# OpenBook_Reader.net
KiCad netlist of a schematic drawn in EAGLE
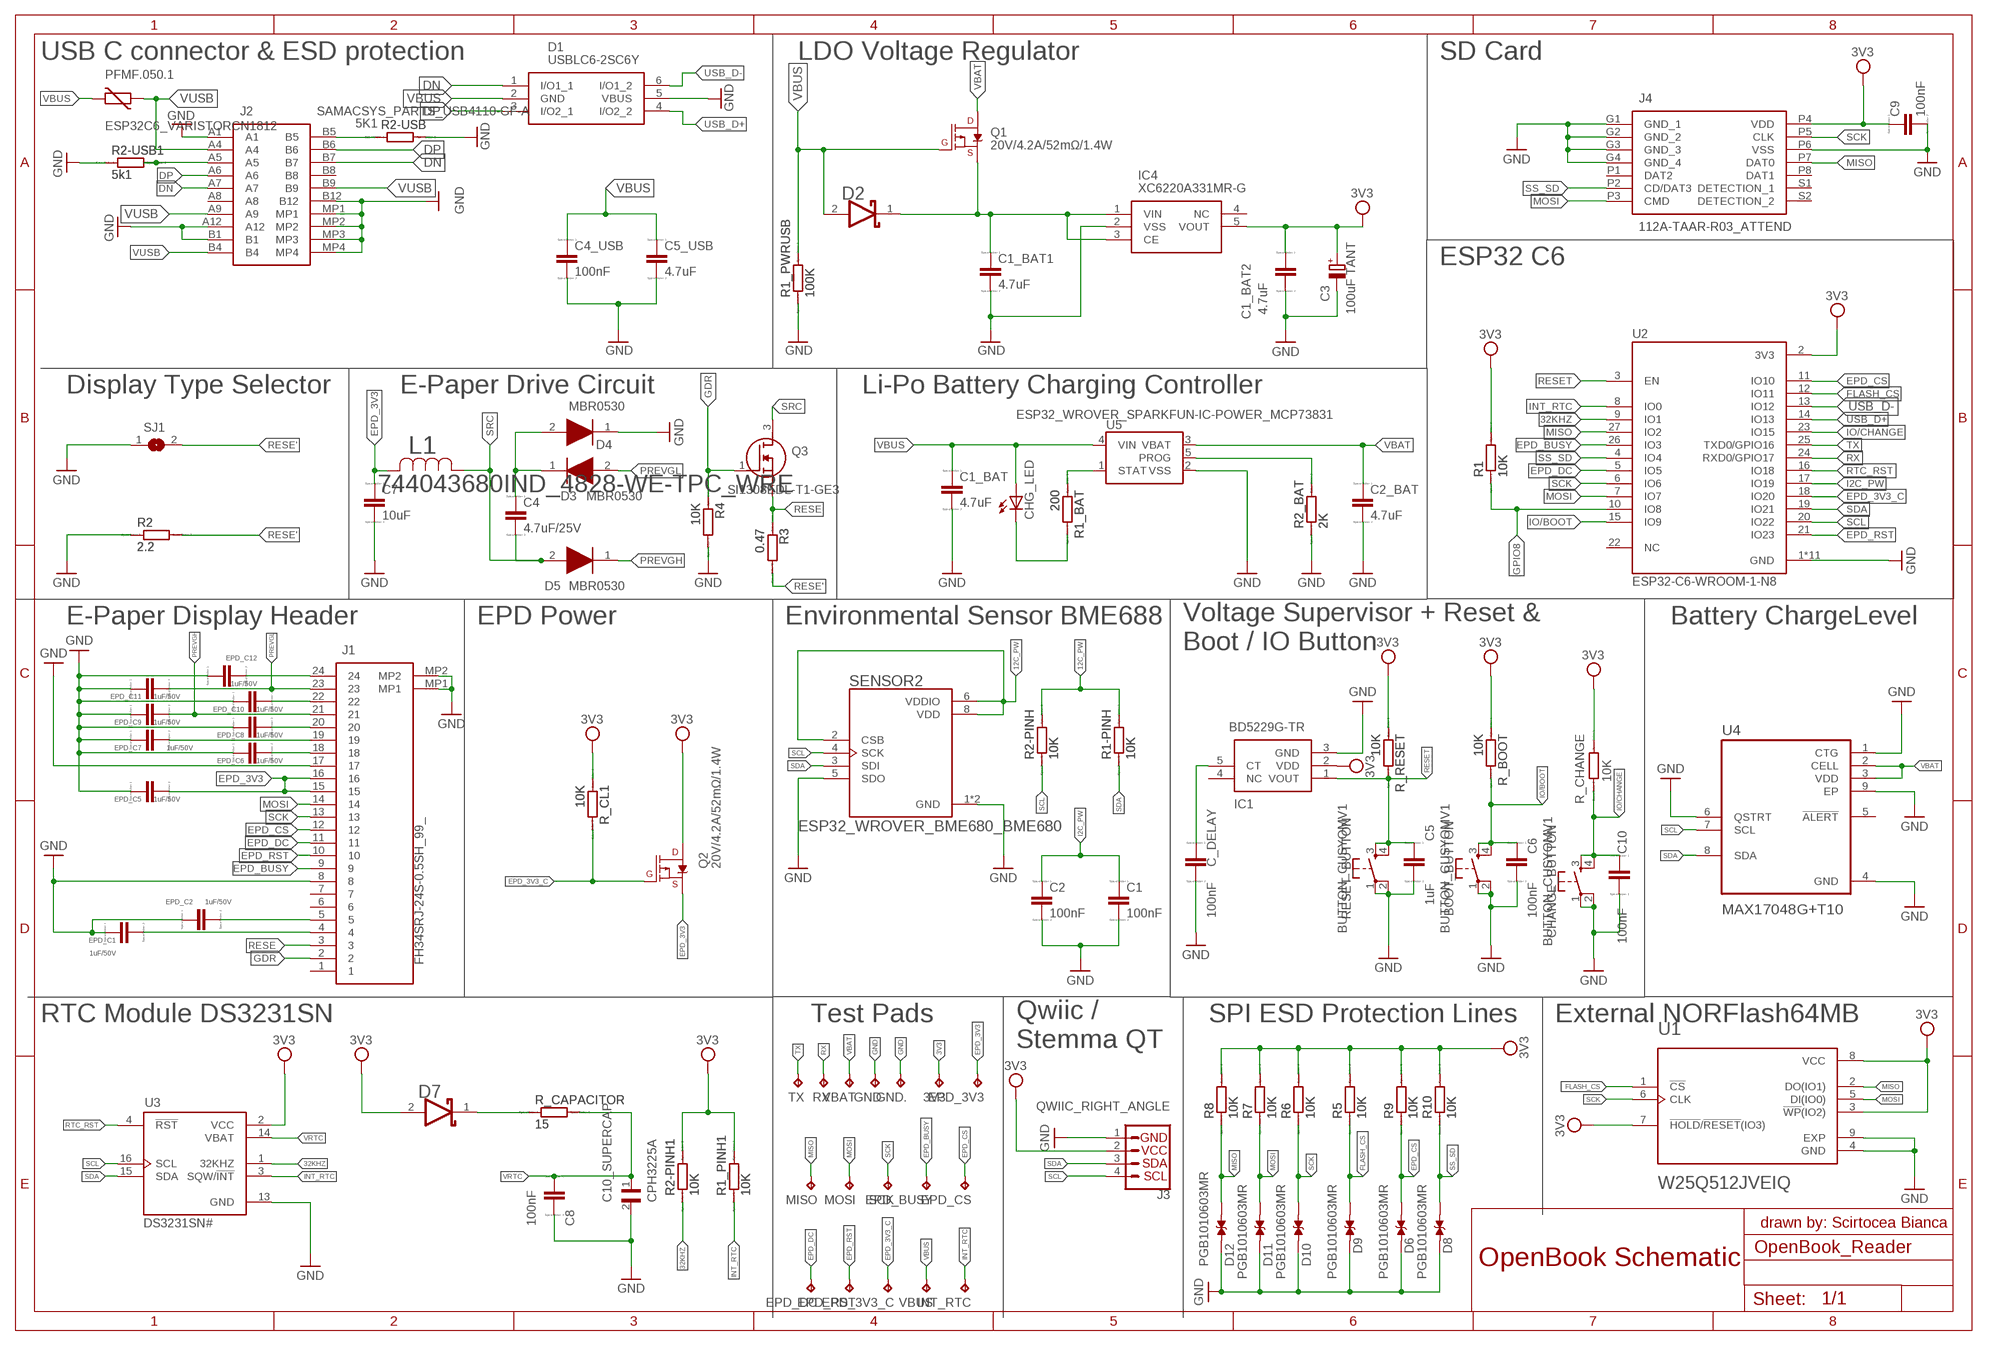
[diagram p0: schematic, sheet 1]

(export (version "E")
  (design (tool "Eeschema 10.0.6"))
  (components
    (comp (ref "3V3")
      (value "TPTP20R")
      (footprint "eagle-import:TP20R")
      (libsource (lib "eagle-import") (part "TPTP20R"))
    )
    (comp (ref "BOOT_BUTTON")
      (value "BUTTON_CUSYOMV1")
      (footprint "eagle-import:MYBUTTON")
      (libsource (lib "eagle-import") (part "BUTTON_CUSYOMV1"))
    )
    (comp (ref "C1")
      (value "100nF")
      (footprint "eagle-import:EAGLE-LTSPICE_C0402")
      (libsource (lib "eagle-import") (part "EAGLE-LTSPICE_CC0402"))
    )
    (comp (ref "C1_BAT")
      (value "4.7uF")
      (footprint "eagle-import:EAGLE-LTSPICE_C0402")
      (libsource (lib "eagle-import") (part "EAGLE-LTSPICE_CC0402"))
    )
    (comp (ref "C1_BAT1")
      (value "4.7uF")
      (footprint "eagle-import:EAGLE-LTSPICE_C0402")
      (libsource (lib "eagle-import") (part "EAGLE-LTSPICE_CC0402"))
    )
    (comp (ref "C1_BAT2")
      (value "4.7uF")
      (footprint "eagle-import:EAGLE-LTSPICE_C0402")
      (libsource (lib "eagle-import") (part "EAGLE-LTSPICE_CC0402"))
    )
    (comp (ref "C2")
      (value "100nF")
      (footprint "eagle-import:EAGLE-LTSPICE_C0402")
      (libsource (lib "eagle-import") (part "EAGLE-LTSPICE_CC0402"))
    )
    (comp (ref "C2_BAT")
      (value "4.7uF")
      (footprint "eagle-import:EAGLE-LTSPICE_C0402")
      (libsource (lib "eagle-import") (part "EAGLE-LTSPICE_CC0402"))
    )
    (comp (ref "C3")
      (value "100uF TANT")
      (footprint "eagle-import:RCL_CT3528")
      (libsource (lib "eagle-import") (part "RCL_CPOL-EUCT3528"))
    )
    (comp (ref "C4")
      (value "4.7uF/25V")
      (footprint "eagle-import:EAGLE-LTSPICE_C0402")
      (libsource (lib "eagle-import") (part "EAGLE-LTSPICE_CC0402"))
    )
    (comp (ref "C4_USB")
      (value "100nF")
      (footprint "eagle-import:EAGLE-LTSPICE_C0402")
      (libsource (lib "eagle-import") (part "EAGLE-LTSPICE_CC0402"))
    )
    (comp (ref "C5")
      (value "1uF")
      (footprint "eagle-import:EAGLE-LTSPICE_C0402")
      (libsource (lib "eagle-import") (part "EAGLE-LTSPICE_CC0402"))
    )
    (comp (ref "C5_USB")
      (value "4.7uF")
      (footprint "eagle-import:EAGLE-LTSPICE_C0402")
      (libsource (lib "eagle-import") (part "EAGLE-LTSPICE_CC0402"))
    )
    (comp (ref "C6")
      (value "100nF")
      (footprint "eagle-import:EAGLE-LTSPICE_C0402")
      (libsource (lib "eagle-import") (part "EAGLE-LTSPICE_CC0402"))
    )
    (comp (ref "C7")
      (value "10uF")
      (footprint "eagle-import:EAGLE-LTSPICE_C0402")
      (libsource (lib "eagle-import") (part "EAGLE-LTSPICE_CC0402"))
    )
    (comp (ref "C8")
      (value "100nF")
      (footprint "eagle-import:EAGLE-LTSPICE_C0402")
      (libsource (lib "eagle-import") (part "EAGLE-LTSPICE_CC0402"))
    )
    (comp (ref "C9")
      (value "100nF")
      (footprint "eagle-import:EAGLE-LTSPICE_C0402")
      (libsource (lib "eagle-import") (part "EAGLE-LTSPICE_CC0402"))
    )
    (comp (ref "C10")
      (value "100nF")
      (footprint "eagle-import:EAGLE-LTSPICE_C0402")
      (libsource (lib "eagle-import") (part "EAGLE-LTSPICE_CC0402"))
    )
    (comp (ref "C10_SUPERCAP")
      (value "CPH3225A")
      (footprint "eagle-import:CAPCP3225X100N")
      (fields (field (name "MF") "Seiko Instruments"))
      (libsource (lib "eagle-import") (part "CPH3225A"))
    )
    (comp (ref "CHANGE_BUTTON")
      (value "BUTTON_CUSYOMV1")
      (footprint "eagle-import:MYBUTTON")
      (libsource (lib "eagle-import") (part "BUTTON_CUSYOMV1"))
    )
    (comp (ref "CHG_LED")
      (value "ADAFRUIT_LEDCHIP-LED0603")
      (footprint "eagle-import:ADAFRUIT_CHIP-LED0603")
      (libsource (lib "eagle-import") (part "ADAFRUIT_LEDCHIP-LED0603"))
    )
    (comp (ref "C_DELAY")
      (value "100nF")
      (footprint "eagle-import:EAGLE-LTSPICE_C0402")
      (libsource (lib "eagle-import") (part "EAGLE-LTSPICE_CC0402"))
    )
    (comp (ref "D1")
      (value "USBLC6-2SC6Y")
      (footprint "eagle-import:SOT95P280X145-6N")
      (fields (field (name "MF") "STMicroelectronics"))
      (libsource (lib "eagle-import") (part "USBLC6-2SC6Y"))
    )
    (comp (ref "D2")
      (value "ESP32_WROVER_AVX---SD0805S020S1R0_AVX_SD0805S020S1R0_0_0AVX_SD0805S020S1R0_0_0")
      (footprint "eagle-import:ESP32_WROVER_AVX---SD0805S020S1R0_AVX_SD0805S020S1R0_0")
      (fields
        (field (name "DIGIKEY_PART_NUMBER") "478-7800-1-ND")
        (field (name "MF") "AVX")
        (field (name "MOUSER_PART_NUMBER") "581-SD0805S020S1R0")
      )
      (libsource (lib "eagle-import") (part "ESP32_WROVER_AVX---SD0805S020S1R0_AVX_SD0805S020S1R0_0_0AVX_SD0805S020S1R0_0_0"))
    )
    (comp (ref "D3")
      (value "MBR0530")
      (footprint "eagle-import:SOD3716X135N")
      (fields (field (name "MF") "ON Semiconductor"))
      (libsource (lib "eagle-import") (part "MBR0530"))
    )
    (comp (ref "D4")
      (value "MBR0530")
      (footprint "eagle-import:SOD3716X135N")
      (fields (field (name "MF") "ON Semiconductor"))
      (libsource (lib "eagle-import") (part "MBR0530"))
    )
    (comp (ref "D5")
      (value "MBR0530")
      (footprint "eagle-import:SOD3716X135N")
      (fields (field (name "MF") "ON Semiconductor"))
      (libsource (lib "eagle-import") (part "MBR0530"))
    )
    (comp (ref "D6")
      (value "PGB1010603MR")
      (footprint "eagle-import:DIOC1608X36N")
      (fields (field (name "MF") "Littelfuse Inc."))
      (libsource (lib "eagle-import") (part "PGB1010603MR"))
    )
    (comp (ref "D7")
      (value "ESP32_WROVER_AVX---SD0805S020S1R0_AVX_SD0805S020S1R0_0_0AVX_SD0805S020S1R0_0_0")
      (footprint "eagle-import:ESP32_WROVER_AVX---SD0805S020S1R0_AVX_SD0805S020S1R0_0")
      (fields
        (field (name "DIGIKEY_PART_NUMBER") "478-7800-1-ND")
        (field (name "MF") "AVX")
        (field (name "MOUSER_PART_NUMBER") "581-SD0805S020S1R0")
      )
      (libsource (lib "eagle-import") (part "ESP32_WROVER_AVX---SD0805S020S1R0_AVX_SD0805S020S1R0_0_0AVX_SD0805S020S1R0_0_0"))
    )
    (comp (ref "D8")
      (value "PGB1010603MR")
      (footprint "eagle-import:DIOC1608X36N")
      (fields (field (name "MF") "Littelfuse Inc."))
      (libsource (lib "eagle-import") (part "PGB1010603MR"))
    )
    (comp (ref "D9")
      (value "PGB1010603MR")
      (footprint "eagle-import:DIOC1608X36N")
      (fields (field (name "MF") "Littelfuse Inc."))
      (libsource (lib "eagle-import") (part "PGB1010603MR"))
    )
    (comp (ref "D10")
      (value "PGB1010603MR")
      (footprint "eagle-import:DIOC1608X36N")
      (fields (field (name "MF") "Littelfuse Inc."))
      (libsource (lib "eagle-import") (part "PGB1010603MR"))
    )
    (comp (ref "D11")
      (value "PGB1010603MR")
      (footprint "eagle-import:DIOC1608X36N")
      (fields (field (name "MF") "Littelfuse Inc."))
      (libsource (lib "eagle-import") (part "PGB1010603MR"))
    )
    (comp (ref "D12")
      (value "PGB1010603MR")
      (footprint "eagle-import:DIOC1608X36N")
      (fields (field (name "MF") "Littelfuse Inc."))
      (libsource (lib "eagle-import") (part "PGB1010603MR"))
    )
    (comp (ref "EPD_3V3")
      (value "TPTP20R")
      (footprint "eagle-import:TP20R")
      (libsource (lib "eagle-import") (part "TPTP20R"))
    )
    (comp (ref "EPD_3V3_C")
      (value "TPTP20R")
      (footprint "eagle-import:TP20R")
      (libsource (lib "eagle-import") (part "TPTP20R"))
    )
    (comp (ref "EPD_BUSY")
      (value "TPTP20R")
      (footprint "eagle-import:TP20R")
      (libsource (lib "eagle-import") (part "TPTP20R"))
    )
    (comp (ref "EPD_C1")
      (value "1uF/50V")
      (footprint "eagle-import:EAGLE-LTSPICE_C0402")
      (libsource (lib "eagle-import") (part "EAGLE-LTSPICE_CC0402"))
    )
    (comp (ref "EPD_C2")
      (value "1uF/50V")
      (footprint "eagle-import:EAGLE-LTSPICE_C0402")
      (libsource (lib "eagle-import") (part "EAGLE-LTSPICE_CC0402"))
    )
    (comp (ref "EPD_C5")
      (value "1uF/50V")
      (footprint "eagle-import:EAGLE-LTSPICE_C0402")
      (libsource (lib "eagle-import") (part "EAGLE-LTSPICE_CC0402"))
    )
    (comp (ref "EPD_C6")
      (value "1uF/50V")
      (footprint "eagle-import:EAGLE-LTSPICE_C0402")
      (libsource (lib "eagle-import") (part "EAGLE-LTSPICE_CC0402"))
    )
    (comp (ref "EPD_C7")
      (value "1uF/50V")
      (footprint "eagle-import:EAGLE-LTSPICE_C0402")
      (libsource (lib "eagle-import") (part "EAGLE-LTSPICE_CC0402"))
    )
    (comp (ref "EPD_C8")
      (value "1uF/50V")
      (footprint "eagle-import:EAGLE-LTSPICE_C0402")
      (libsource (lib "eagle-import") (part "EAGLE-LTSPICE_CC0402"))
    )
    (comp (ref "EPD_C9")
      (value "1uF/50V")
      (footprint "eagle-import:EAGLE-LTSPICE_C0402")
      (libsource (lib "eagle-import") (part "EAGLE-LTSPICE_CC0402"))
    )
    (comp (ref "EPD_C10")
      (value "1uF/50V")
      (footprint "eagle-import:EAGLE-LTSPICE_C0402")
      (libsource (lib "eagle-import") (part "EAGLE-LTSPICE_CC0402"))
    )
    (comp (ref "EPD_C11")
      (value "1uF/50V")
      (footprint "eagle-import:EAGLE-LTSPICE_C0402")
      (libsource (lib "eagle-import") (part "EAGLE-LTSPICE_CC0402"))
    )
    (comp (ref "EPD_C12")
      (value "1uF/50V")
      (footprint "eagle-import:EAGLE-LTSPICE_C0402")
      (libsource (lib "eagle-import") (part "EAGLE-LTSPICE_CC0402"))
    )
    (comp (ref "EPD_CS")
      (value "TPTP20R")
      (footprint "eagle-import:TP20R")
      (libsource (lib "eagle-import") (part "TPTP20R"))
    )
    (comp (ref "EPD_DC")
      (value "TPTP20R")
      (footprint "eagle-import:TP20R")
      (libsource (lib "eagle-import") (part "TPTP20R"))
    )
    (comp (ref "EPD_RST")
      (value "TPTP20R")
      (footprint "eagle-import:TP20R")
      (libsource (lib "eagle-import") (part "TPTP20R"))
    )
    (comp (ref "GND")
      (value "TPTP20R")
      (footprint "eagle-import:TP20R")
      (libsource (lib "eagle-import") (part "TPTP20R"))
    )
    (comp (ref "GND.")
      (value "TPTP20R")
      (footprint "eagle-import:TP20R")
      (libsource (lib "eagle-import") (part "TPTP20R"))
    )
    (comp (ref "IC1")
      (value "BD5229G-TR")
      (footprint "eagle-import:SOT95P280X125-5N")
      (fields (field (name "MOUSER_PART_NUMBER") "755-BD5229G-TR"))
      (libsource (lib "eagle-import") (part "BD5229G-TR"))
    )
    (comp (ref "IC4")
      (value "XC6220A331MR-G")
      (footprint "eagle-import:SOT95P280X120-5N")
      (fields (field (name "MOUSER_PART_NUMBER") "865-XC6220A331MR-G"))
      (libsource (lib "eagle-import") (part "XC6220A331MR-G"))
    )
    (comp (ref "INT_RTC")
      (value "TPTP20R")
      (footprint "eagle-import:TP20R")
      (libsource (lib "eagle-import") (part "TPTP20R"))
    )
    (comp (ref "J1")
      (value "FH34SRJ-24S-0.5SH_99_")
      (footprint "eagle-import:FH34SRJ24S05SH99")
      (fields
        (field (name "MANUFACTURER_PART_NUMBER") "FH34SRJ-24S-0.5SH(99)")
        (field (name "MOUSER_PART_NUMBER") "798-FH34SRJ24S05SH99")
      )
      (libsource (lib "eagle-import") (part "FH34SRJ-24S-0.5SH_99_"))
    )
    (comp (ref "J2")
      (value "SAMACSYS_PARTS_USB4110-GF-A")
      (footprint "eagle-import:SAMACSYS_PARTS_USB4110GFA")
      (fields
        (field (name "MANUFACTURER_PART_NUMBER") "USB4110-GF-A")
        (field (name "MOUSER_PART_NUMBER") "640-USB4110-GF-A")
      )
      (libsource (lib "eagle-import") (part "SAMACSYS_PARTS_USB4110-GF-A"))
    )
    (comp (ref "J3")
      (value "QWIIC_RIGHT_ANGLE")
      (footprint "eagle-import:JST04_1MM_RA")
      (libsource (lib "eagle-import") (part "QWIIC_CONNECTORJS-1MM"))
    )
    (comp (ref "J4")
      (value "112A-TAAR-R03_ATTEND")
      (footprint "eagle-import:112ATAARR03ATTEND")
      (fields (field (name "MANUFACTURER_PART_NUMBER") "112A-TAAR-R03 ATTEND"))
      (libsource (lib "eagle-import") (part "112A-TAAR-R03_ATTEND"))
    )
    (comp (ref "L1")
      (value "744043680IND_4828-WE-TPC_WRE")
      (footprint "eagle-import:IND_4828-WE-TPC_WRE")
      (fields
        (field (name "MANUFACTURER_PART_NUMBER") "744043680")
        (field (name "COPYRIGHT") "Copyright (C) 2024 Ultra Librarian. All rights reserved.")
      )
      (libsource (lib "eagle-import") (part "744043680IND_4828-WE-TPC_WRE"))
    )
    (comp (ref "MISO")
      (value "TPTP20R")
      (footprint "eagle-import:TP20R")
      (libsource (lib "eagle-import") (part "TPTP20R"))
    )
    (comp (ref "MOSI")
      (value "TPTP20R")
      (footprint "eagle-import:TP20R")
      (libsource (lib "eagle-import") (part "TPTP20R"))
    )
    (comp (ref "PFMF.050.1")
      (value "ESP32C6_VARISTORCN1812")
      (footprint "eagle-import:ESP32C6_VARISTOR_CT_CN1812")
      (libsource (lib "eagle-import") (part "ESP32C6_VARISTORCN1812"))
    )
    (comp (ref "Q1")
      (value "20V/4.2A/52mΩ/1.4W")
      (footprint "eagle-import:ESP32_WROVER_SPARKFUN-DISCRETESEMI_SOT23-3")
      (libsource (lib "eagle-import") (part "ESP32_WROVER_SPARKFUN-DISCRETESEMI_MOSFET_PCH-DMG2305UX-7"))
    )
    (comp (ref "Q2")
      (value "20V/4.2A/52mΩ/1.4W")
      (footprint "eagle-import:ESP32_WROVER_SPARKFUN-DISCRETESEMI_SOT23-3")
      (libsource (lib "eagle-import") (part "ESP32_WROVER_SPARKFUN-DISCRETESEMI_MOSFET_PCH-DMG2305UX-7"))
    )
    (comp (ref "Q3")
      (value "SI1308EDL-T1-GE3")
      (footprint "eagle-import:SOT65P210X110-3N")
      (fields (field (name "MF") "Vishay Siliconix"))
      (libsource (lib "eagle-import") (part "SI1308EDL-T1-GE3"))
    )
    (comp (ref "R1")
      (value "10K")
      (footprint "eagle-import:ESP32_WROVER_EAGLE-LTSPICE_R0402")
      (libsource (lib "eagle-import") (part "ESP32_WROVER_EAGLE-LTSPICE_RR0402"))
    )
    (comp (ref "R1-PINH")
      (value "10K")
      (footprint "eagle-import:ESP32_WROVER_EAGLE-LTSPICE_R0402")
      (libsource (lib "eagle-import") (part "ESP32_WROVER_EAGLE-LTSPICE_RR0402"))
    )
    (comp (ref "R1_BAT")
      (value "200")
      (footprint "eagle-import:ESP32_WROVER_EAGLE-LTSPICE_R0402")
      (libsource (lib "eagle-import") (part "ESP32_WROVER_EAGLE-LTSPICE_RR0402"))
    )
    (comp (ref "R1_PINH1")
      (value "10K")
      (footprint "eagle-import:ESP32_WROVER_EAGLE-LTSPICE_R0402")
      (libsource (lib "eagle-import") (part "ESP32_WROVER_EAGLE-LTSPICE_RR0402"))
    )
    (comp (ref "R1_PWRUSB")
      (value "100K")
      (footprint "eagle-import:ESP32_WROVER_EAGLE-LTSPICE_R0402")
      (libsource (lib "eagle-import") (part "ESP32_WROVER_EAGLE-LTSPICE_RR0402"))
    )
    (comp (ref "R2")
      (value "2.2")
      (footprint "eagle-import:ESP32_WROVER_EAGLE-LTSPICE_R0402")
      (libsource (lib "eagle-import") (part "ESP32_WROVER_EAGLE-LTSPICE_RR0402"))
    )
    (comp (ref "R2-PINH")
      (value "10K")
      (footprint "eagle-import:ESP32_WROVER_EAGLE-LTSPICE_R0402")
      (libsource (lib "eagle-import") (part "ESP32_WROVER_EAGLE-LTSPICE_RR0402"))
    )
    (comp (ref "R2-PINH1")
      (value "10K")
      (footprint "eagle-import:ESP32_WROVER_EAGLE-LTSPICE_R0402")
      (libsource (lib "eagle-import") (part "ESP32_WROVER_EAGLE-LTSPICE_RR0402"))
    )
    (comp (ref "R2-USB")
      (value "5K1")
      (footprint "eagle-import:ESP32_WROVER_EAGLE-LTSPICE_R0402")
      (libsource (lib "eagle-import") (part "ESP32_WROVER_EAGLE-LTSPICE_RR0402"))
    )
    (comp (ref "R2-USB1")
      (value "5k1")
      (footprint "eagle-import:ESP32_WROVER_EAGLE-LTSPICE_R0402")
      (libsource (lib "eagle-import") (part "ESP32_WROVER_EAGLE-LTSPICE_RR0402"))
    )
    (comp (ref "R2_BAT")
      (value "2K")
      (footprint "eagle-import:ESP32_WROVER_EAGLE-LTSPICE_R0402")
      (libsource (lib "eagle-import") (part "ESP32_WROVER_EAGLE-LTSPICE_RR0402"))
    )
    (comp (ref "R3")
      (value "0.47")
      (footprint "eagle-import:ESP32_WROVER_EAGLE-LTSPICE_R0402")
      (libsource (lib "eagle-import") (part "ESP32_WROVER_EAGLE-LTSPICE_RR0402"))
    )
    (comp (ref "R4")
      (value "10K")
      (footprint "eagle-import:ESP32_WROVER_EAGLE-LTSPICE_R0402")
      (libsource (lib "eagle-import") (part "ESP32_WROVER_EAGLE-LTSPICE_RR0402"))
    )
    (comp (ref "R5")
      (value "10K")
      (footprint "eagle-import:ESP32_WROVER_EAGLE-LTSPICE_R0402")
      (libsource (lib "eagle-import") (part "ESP32_WROVER_EAGLE-LTSPICE_RR0402"))
    )
    (comp (ref "R6")
      (value "10K")
      (footprint "eagle-import:ESP32_WROVER_EAGLE-LTSPICE_R0402")
      (libsource (lib "eagle-import") (part "ESP32_WROVER_EAGLE-LTSPICE_RR0402"))
    )
    (comp (ref "R7")
      (value "10K")
      (footprint "eagle-import:ESP32_WROVER_EAGLE-LTSPICE_R0402")
      (libsource (lib "eagle-import") (part "ESP32_WROVER_EAGLE-LTSPICE_RR0402"))
    )
    (comp (ref "R8")
      (value "10K")
      (footprint "eagle-import:ESP32_WROVER_EAGLE-LTSPICE_R0402")
      (libsource (lib "eagle-import") (part "ESP32_WROVER_EAGLE-LTSPICE_RR0402"))
    )
    (comp (ref "R9")
      (value "10K")
      (footprint "eagle-import:ESP32_WROVER_EAGLE-LTSPICE_R0402")
      (libsource (lib "eagle-import") (part "ESP32_WROVER_EAGLE-LTSPICE_RR0402"))
    )
    (comp (ref "R10")
      (value "10K")
      (footprint "eagle-import:ESP32_WROVER_EAGLE-LTSPICE_R0402")
      (libsource (lib "eagle-import") (part "ESP32_WROVER_EAGLE-LTSPICE_RR0402"))
    )
    (comp (ref "RESET_BUTTON")
      (value "BUTTON_CUSYOMV1")
      (footprint "eagle-import:MYBUTTON")
      (libsource (lib "eagle-import") (part "BUTTON_CUSYOMV1"))
    )
    (comp (ref "RX")
      (value "TPTP20R")
      (footprint "eagle-import:TP20R")
      (libsource (lib "eagle-import") (part "TPTP20R"))
    )
    (comp (ref "R_BOOT")
      (value "10K")
      (footprint "eagle-import:ESP32_WROVER_EAGLE-LTSPICE_R0402")
      (libsource (lib "eagle-import") (part "ESP32_WROVER_EAGLE-LTSPICE_RR0402"))
    )
    (comp (ref "R_CAPACITOR")
      (value "15")
      (footprint "eagle-import:ESP32_WROVER_EAGLE-LTSPICE_R0402")
      (libsource (lib "eagle-import") (part "ESP32_WROVER_EAGLE-LTSPICE_RR0402"))
    )
    (comp (ref "R_CHANGE")
      (value "10K")
      (footprint "eagle-import:ESP32_WROVER_EAGLE-LTSPICE_R0402")
      (libsource (lib "eagle-import") (part "ESP32_WROVER_EAGLE-LTSPICE_RR0402"))
    )
    (comp (ref "R_CL1")
      (value "10K")
      (footprint "eagle-import:ESP32_WROVER_EAGLE-LTSPICE_R0402")
      (libsource (lib "eagle-import") (part "ESP32_WROVER_EAGLE-LTSPICE_RR0402"))
    )
    (comp (ref "R_RESET")
      (value "10K")
      (footprint "eagle-import:ESP32_WROVER_EAGLE-LTSPICE_R0402")
      (libsource (lib "eagle-import") (part "ESP32_WROVER_EAGLE-LTSPICE_RR0402"))
    )
    (comp (ref "SCK")
      (value "TPTP20R")
      (footprint "eagle-import:TP20R")
      (libsource (lib "eagle-import") (part "TPTP20R"))
    )
    (comp (ref "SENSOR2")
      (value "ESP32_WROVER_BME680_BME680")
      (footprint "eagle-import:ESP32_WROVER_BME680_PSON80P300X300X100-8N")
      (fields (field (name "MF") "Bosch Sensortec") (field (name "MP") "BME680"))
      (libsource (lib "eagle-import") (part "ESP32_WROVER_BME680_BME680"))
    )
    (comp (ref "SJ1") (value "SJ") (footprint "eagle-import:SJ") (libsource (lib "eagle-import") (part "SJ")))
    (comp (ref "TX")
      (value "TPTP20R")
      (footprint "eagle-import:TP20R")
      (libsource (lib "eagle-import") (part "TPTP20R"))
    )
    (comp (ref "U1")
      (value "W25Q512JVEIQ")
      (footprint "eagle-import:SON127P600X800X80-9N")
      (fields (field (name "MF") "Winbond Electronics"))
      (libsource (lib "eagle-import") (part "W25Q512JVEIQ"))
    )
    (comp (ref "U2")
      (value "ESP32-C6-WROOM-1-N8")
      (footprint "eagle-import:XCVR_ESP32-C6-WROOM-1-N8")
      (fields (field (name "MF") "Espressif Systems"))
      (libsource (lib "eagle-import") (part "ESP32-C6-WROOM-1-N8"))
    )
    (comp (ref "U3")
      (value "DS3231SN#")
      (footprint "eagle-import:SOIC127P1032X265-16N")
      (fields (field (name "MF") "Analog Devices"))
      (libsource (lib "eagle-import") (part "DS3231SN#"))
    )
    (comp (ref "U4")
      (value "MAX17048G+T10")
      (footprint "eagle-import:SON50P200X200X80-9N")
      (fields (field (name "MF") "Analog Devices"))
      (libsource (lib "eagle-import") (part "MAX17048G+T10"))
    )
    (comp (ref "U5")
      (value "ESP32_WROVER_SPARKFUN-IC-POWER_MCP73831")
      (footprint "eagle-import:ESP32_WROVER_SPARKFUN-IC-POWER_SOT23-5")
      (libsource (lib "eagle-import") (part "ESP32_WROVER_SPARKFUN-IC-POWER_MCP73831"))
    )
    (comp (ref "VBAT")
      (value "TPTP20R")
      (footprint "eagle-import:TP20R")
      (libsource (lib "eagle-import") (part "TPTP20R"))
    )
    (comp (ref "VBUS")
      (value "TPTP20R")
      (footprint "eagle-import:TP20R")
      (libsource (lib "eagle-import") (part "TPTP20R"))
    )
  )
  (nets
    (net (code "1") (name "3V3") (class "Default")
      (node (ref "3V3") (pin "TP") (pinfunction "TP_TP") (pintype "input"))
      (node (ref "C1_BAT2") (pin "1") (pinfunction "1_1") (pintype "passive"))
      (node (ref "C3") (pin "+") (pinfunction "+_+") (pintype "passive"))
      (node (ref "C9") (pin "1") (pinfunction "1_1") (pintype "passive"))
      (node (ref "D7") (pin "2") (pinfunction "ANODE_2") (pintype "bidirectional"))
      (node (ref "IC1") (pin "2") (pinfunction "VDD_2") (pintype "bidirectional"))
      (node (ref "IC4") (pin "5") (pinfunction "VOUT_5") (pintype "bidirectional"))
      (node (ref "J3") (pin "2") (pinfunction "2_2") (pintype "power_in"))
      (node (ref "J4") (pin "P4") (pinfunction "VDD_P4") (pintype "bidirectional"))
      (node (ref "Q2") (pin "3") (pinfunction "D_3") (pintype "bidirectional"))
      (node (ref "R1") (pin "2") (pinfunction "2_2") (pintype "passive"))
      (node (ref "R10") (pin "2") (pinfunction "2_2") (pintype "passive"))
      (node (ref "R1_PINH1") (pin "2") (pinfunction "2_2") (pintype "passive"))
      (node (ref "R2-PINH1") (pin "2") (pinfunction "2_2") (pintype "passive"))
      (node (ref "R5") (pin "2") (pinfunction "2_2") (pintype "passive"))
      (node (ref "R6") (pin "2") (pinfunction "2_2") (pintype "passive"))
      (node (ref "R7") (pin "2") (pinfunction "2_2") (pintype "passive"))
      (node (ref "R8") (pin "2") (pinfunction "2_2") (pintype "passive"))
      (node (ref "R9") (pin "2") (pinfunction "2_2") (pintype "passive"))
      (node (ref "R_BOOT") (pin "1") (pinfunction "1_1") (pintype "passive"))
      (node (ref "R_CHANGE") (pin "1") (pinfunction "1_1") (pintype "passive"))
      (node (ref "R_CL1") (pin "1") (pinfunction "1_1") (pintype "passive"))
      (node (ref "R_RESET") (pin "1") (pinfunction "1_1") (pintype "passive"))
      (node (ref "U1") (pin "3") (pinfunction "~{WP}(IO2)_3") (pintype "bidirectional"))
      (node (ref "U1") (pin "7") (pinfunction "~{HOLD}/~{RESET}(IO3)_7") (pintype "bidirectional"))
      (node (ref "U1") (pin "8") (pinfunction "VCC_8") (pintype "power_in"))
      (node (ref "U2") (pin "2") (pinfunction "3V3_2") (pintype "power_in"))
      (node (ref "U3") (pin "2") (pinfunction "VCC_2") (pintype "power_in"))
    )
    (net (code "2") (name "12C_PW") (class "Default")
      (node (ref "R1-PINH") (pin "2") (pinfunction "2_2") (pintype "passive"))
      (node (ref "R2-PINH") (pin "2") (pinfunction "2_2") (pintype "passive"))
      (node (ref "SENSOR2") (pin "2") (pinfunction "CSB_2") (pintype "input"))
      (node (ref "SENSOR2") (pin "6") (pinfunction "VDDIO_6") (pintype "power_in"))
      (node (ref "SENSOR2") (pin "8") (pinfunction "VDD_8") (pintype "power_in"))
    )
    (net (code "3") (name "32KHZ") (class "Default")
      (node (ref "R2-PINH1") (pin "1") (pinfunction "1_1") (pintype "passive"))
      (node (ref "U2") (pin "9") (pinfunction "IO1_9") (pintype "bidirectional"))
      (node (ref "U3") (pin "1") (pinfunction "32KHZ_1") (pintype "output"))
    )
    (net (code "4") (name "DN") (class "Default")
      (node (ref "D1") (pin "1") (pinfunction "I/O1_1_1") (pintype "bidirectional"))
      (node (ref "J2") (pin "A7") (pinfunction "A7_A7") (pintype "bidirectional"))
      (node (ref "J2") (pin "B7") (pinfunction "B7_B7") (pintype "bidirectional"))
    )
    (net (code "5") (name "DP") (class "Default")
      (node (ref "D1") (pin "3") (pinfunction "I/O2_1_3") (pintype "bidirectional"))
      (node (ref "J2") (pin "A6") (pinfunction "A6_A6") (pintype "bidirectional"))
      (node (ref "J2") (pin "B6") (pinfunction "B6_B6") (pintype "bidirectional"))
    )
    (net (code "6") (name "EPD_3V3") (class "Default")
      (node (ref "C7") (pin "1") (pinfunction "1_1") (pintype "passive"))
      (node (ref "EPD_3V3") (pin "TP") (pinfunction "TP_TP") (pintype "input"))
      (node (ref "EPD_C5") (pin "2") (pinfunction "2_2") (pintype "passive"))
      (node (ref "J1") (pin "15") (pinfunction "15_15") (pintype "bidirectional"))
      (node (ref "J1") (pin "16") (pinfunction "16_16") (pintype "bidirectional"))
      (node (ref "L1") (pin "2") (pinfunction "2_2") (pintype "passive"))
      (node (ref "Q2") (pin "2") (pinfunction "S_2") (pintype "bidirectional"))
    )
    (net (code "7") (name "EPD_3V3_C") (class "Default")
      (node (ref "EPD_3V3_C") (pin "TP") (pinfunction "TP_TP") (pintype "input"))
      (node (ref "Q2") (pin "1") (pinfunction "G_1") (pintype "bidirectional"))
      (node (ref "R_CL1") (pin "2") (pinfunction "2_2") (pintype "passive"))
      (node (ref "U2") (pin "18") (pinfunction "IO20_18") (pintype "bidirectional"))
    )
    (net (code "8") (name "EPD_BUSY") (class "Default")
      (node (ref "EPD_BUSY") (pin "TP") (pinfunction "TP_TP") (pintype "input"))
      (node (ref "J1") (pin "9") (pinfunction "9_9") (pintype "bidirectional"))
      (node (ref "U2") (pin "26") (pinfunction "IO3_26") (pintype "bidirectional"))
    )
    (net (code "9") (name "EPD_CS") (class "Default")
      (node (ref "D6") (pin "2") (pinfunction "2_2") (pintype "passive"))
      (node (ref "EPD_CS") (pin "TP") (pinfunction "TP_TP") (pintype "input"))
      (node (ref "J1") (pin "12") (pinfunction "12_12") (pintype "bidirectional"))
      (node (ref "R9") (pin "1") (pinfunction "1_1") (pintype "passive"))
      (node (ref "U2") (pin "11") (pinfunction "IO10_11") (pintype "bidirectional"))
    )
    (net (code "10") (name "EPD_DC") (class "Default")
      (node (ref "EPD_DC") (pin "TP") (pinfunction "TP_TP") (pintype "input"))
      (node (ref "J1") (pin "11") (pinfunction "11_11") (pintype "bidirectional"))
      (node (ref "U2") (pin "5") (pinfunction "IO5_5") (pintype "bidirectional"))
    )
    (net (code "11") (name "EPD_RST") (class "Default")
      (node (ref "EPD_RST") (pin "TP") (pinfunction "TP_TP") (pintype "input"))
      (node (ref "J1") (pin "10") (pinfunction "10_10") (pintype "bidirectional"))
      (node (ref "U2") (pin "21") (pinfunction "IO23_21") (pintype "bidirectional"))
    )
    (net (code "12") (name "FLASH_CS") (class "Default")
      (node (ref "D9") (pin "2") (pinfunction "2_2") (pintype "passive"))
      (node (ref "R5") (pin "1") (pinfunction "1_1") (pintype "passive"))
      (node (ref "U1") (pin "1") (pinfunction "~{CS}_1") (pintype "input"))
      (node (ref "U2") (pin "12") (pinfunction "IO11_12") (pintype "bidirectional"))
    )
    (net (code "13") (name "GDR") (class "Default")
      (node (ref "J1") (pin "2") (pinfunction "2_2") (pintype "bidirectional"))
      (node (ref "Q3") (pin "1") (pinfunction "G_1") (pintype "bidirectional"))
      (node (ref "R4") (pin "1") (pinfunction "1_1") (pintype "passive"))
    )
    (net (code "14") (name "GND") (class "Default")
      (node (ref "BOOT_BUTTON") (pin "1") (pinfunction "1_1") (pintype "passive"))
      (node (ref "BOOT_BUTTON") (pin "2") (pinfunction "2_2") (pintype "passive"))
      (node (ref "C1") (pin "2") (pinfunction "2_2") (pintype "passive"))
      (node (ref "C10") (pin "2") (pinfunction "2_2") (pintype "passive"))
      (node (ref "C10_SUPERCAP") (pin "2") (pinfunction "2_2") (pintype "passive"))
      (node (ref "C1_BAT") (pin "2") (pinfunction "2_2") (pintype "passive"))
      (node (ref "C1_BAT1") (pin "2") (pinfunction "2_2") (pintype "passive"))
      (node (ref "C1_BAT2") (pin "2") (pinfunction "2_2") (pintype "passive"))
      (node (ref "C2") (pin "2") (pinfunction "2_2") (pintype "passive"))
      (node (ref "C2_BAT") (pin "2") (pinfunction "2_2") (pintype "passive"))
      (node (ref "C3") (pin "-") (pinfunction "-_-") (pintype "passive"))
      (node (ref "C4_USB") (pin "2") (pinfunction "2_2") (pintype "passive"))
      (node (ref "C5") (pin "2") (pinfunction "2_2") (pintype "passive"))
      (node (ref "C5_USB") (pin "2") (pinfunction "2_2") (pintype "passive"))
      (node (ref "C6") (pin "2") (pinfunction "2_2") (pintype "passive"))
      (node (ref "C7") (pin "2") (pinfunction "2_2") (pintype "passive"))
      (node (ref "C8") (pin "2") (pinfunction "2_2") (pintype "passive"))
      (node (ref "C9") (pin "2") (pinfunction "2_2") (pintype "passive"))
      (node (ref "CHANGE_BUTTON") (pin "1") (pinfunction "1_1") (pintype "passive"))
      (node (ref "CHANGE_BUTTON") (pin "2") (pinfunction "2_2") (pintype "passive"))
      (node (ref "C_DELAY") (pin "2") (pinfunction "2_2") (pintype "passive"))
      (node (ref "D1") (pin "5") (pinfunction "VBUS_5") (pintype "bidirectional"))
      (node (ref "D10") (pin "1") (pinfunction "1_1") (pintype "passive"))
      (node (ref "D11") (pin "1") (pinfunction "1_1") (pintype "passive"))
      (node (ref "D12") (pin "1") (pinfunction "1_1") (pintype "passive"))
      (node (ref "D4") (pin "1") (pinfunction "K_1") (pintype "bidirectional"))
      (node (ref "D6") (pin "1") (pinfunction "1_1") (pintype "passive"))
      (node (ref "D8") (pin "1") (pinfunction "1_1") (pintype "passive"))
      (node (ref "D9") (pin "1") (pinfunction "1_1") (pintype "passive"))
      (node (ref "EPD_C1") (pin "1") (pinfunction "1_1") (pintype "passive"))
      (node (ref "EPD_C10") (pin "1") (pinfunction "1_1") (pintype "passive"))
      (node (ref "EPD_C11") (pin "1") (pinfunction "1_1") (pintype "passive"))
      (node (ref "EPD_C12") (pin "1") (pinfunction "1_1") (pintype "passive"))
      (node (ref "EPD_C2") (pin "1") (pinfunction "1_1") (pintype "passive"))
      (node (ref "EPD_C5") (pin "1") (pinfunction "1_1") (pintype "passive"))
      (node (ref "EPD_C6") (pin "1") (pinfunction "1_1") (pintype "passive"))
      (node (ref "EPD_C7") (pin "1") (pinfunction "1_1") (pintype "passive"))
      (node (ref "EPD_C8") (pin "1") (pinfunction "1_1") (pintype "passive"))
      (node (ref "EPD_C9") (pin "1") (pinfunction "1_1") (pintype "passive"))
      (node (ref "GND") (pin "TP") (pinfunction "TP_TP") (pintype "input"))
      (node (ref "GND.") (pin "TP") (pinfunction "TP_TP") (pintype "input"))
      (node (ref "IC1") (pin "3") (pinfunction "GND_3") (pintype "bidirectional"))
      (node (ref "IC4") (pin "2") (pinfunction "VSS_2") (pintype "bidirectional"))
      (node (ref "J1") (pin "17") (pinfunction "17_17") (pintype "bidirectional"))
      (node (ref "J1") (pin "8") (pinfunction "8_8") (pintype "bidirectional"))
      (node (ref "J1") (pin "MP1") (pinfunction "MP1_MP1") (pintype "bidirectional"))
      (node (ref "J1") (pin "MP2") (pinfunction "MP2_MP2") (pintype "bidirectional"))
      (node (ref "J2") (pin "A1") (pinfunction "A1_A1") (pintype "bidirectional"))
      (node (ref "J2") (pin "A12") (pinfunction "A12_A12") (pintype "bidirectional"))
      (node (ref "J2") (pin "B1") (pinfunction "B1_B1") (pintype "bidirectional"))
      (node (ref "J2") (pin "B12") (pinfunction "B12_B12") (pintype "bidirectional"))
      (node (ref "J2") (pin "MP1") (pinfunction "MP1_MP1") (pintype "bidirectional"))
      (node (ref "J2") (pin "MP2") (pinfunction "MP2_MP2") (pintype "bidirectional"))
      (node (ref "J2") (pin "MP3") (pinfunction "MP3_MP3") (pintype "bidirectional"))
      (node (ref "J2") (pin "MP4") (pinfunction "MP4_MP4") (pintype "bidirectional"))
      (node (ref "J3") (pin "1") (pinfunction "1_1") (pintype "power_in"))
      (node (ref "J4") (pin "G1") (pinfunction "GND_1_G1") (pintype "bidirectional"))
      (node (ref "J4") (pin "G2") (pinfunction "GND_2_G2") (pintype "bidirectional"))
      (node (ref "J4") (pin "G3") (pinfunction "GND_3_G3") (pintype "bidirectional"))
      (node (ref "J4") (pin "G4") (pinfunction "GND_4_G4") (pintype "bidirectional"))
      (node (ref "J4") (pin "P6") (pinfunction "VSS_P6") (pintype "bidirectional"))
      (node (ref "R1_PWRUSB") (pin "1") (pinfunction "1_1") (pintype "passive"))
      (node (ref "R2") (pin "1") (pinfunction "1_1") (pintype "passive"))
      (node (ref "R2-USB") (pin "2") (pinfunction "2_2") (pintype "passive"))
      (node (ref "R2-USB1") (pin "1") (pinfunction "1_1") (pintype "passive"))
      (node (ref "R2_BAT") (pin "1") (pinfunction "1_1") (pintype "passive"))
      (node (ref "R4") (pin "2") (pinfunction "2_2") (pintype "passive"))
      (node (ref "RESET_BUTTON") (pin "1") (pinfunction "1_1") (pintype "passive"))
      (node (ref "RESET_BUTTON") (pin "2") (pinfunction "2_2") (pintype "passive"))
      (node (ref "SENSOR2") (pin "1") (pinfunction "GND_1") (pintype "power_in"))
      (node (ref "SENSOR2") (pin "5") (pinfunction "SDO_5") (pintype "bidirectional"))
      (node (ref "SENSOR2") (pin "7") (pinfunction "GND_7") (pintype "power_in"))
      (node (ref "SJ1") (pin "1") (pinfunction "1_1") (pintype "passive"))
      (node (ref "U1") (pin "4") (pinfunction "GND_4") (pintype "power_in"))
      (node (ref "U1") (pin "9") (pinfunction "EXP_9") (pintype "passive"))
      (node (ref "U2") (pin "1") (pinfunction "GND_1") (pintype "power_in"))
      (node (ref "U2") (pin "28") (pinfunction "GND_28") (pintype "power_in"))
      (node (ref "U2") (pin "29_1") (pinfunction "GND_29_1") (pintype "power_in"))
      (node (ref "U2") (pin "29_2") (pinfunction "GND_29_2") (pintype "power_in"))
      (node (ref "U2") (pin "29_3") (pinfunction "GND_29_3") (pintype "power_in"))
      (node (ref "U2") (pin "29_4") (pinfunction "GND_29_4") (pintype "power_in"))
      (node (ref "U2") (pin "29_5") (pinfunction "GND_29_5") (pintype "power_in"))
      (node (ref "U2") (pin "29_6") (pinfunction "GND_29_6") (pintype "power_in"))
      (node (ref "U2") (pin "29_7") (pinfunction "GND_29_7") (pintype "power_in"))
      (node (ref "U2") (pin "29_8") (pinfunction "GND_29_8") (pintype "power_in"))
      (node (ref "U2") (pin "29_9") (pinfunction "GND_29_9") (pintype "power_in"))
      (node (ref "U3") (pin "13") (pinfunction "GND_13") (pintype "power_in"))
      (node (ref "U4") (pin "1") (pinfunction "CTG_1") (pintype "power_in"))
      (node (ref "U4") (pin "4") (pinfunction "GND_4") (pintype "power_in"))
      (node (ref "U4") (pin "6") (pinfunction "QSTRT_6") (pintype "input"))
      (node (ref "U4") (pin "9") (pinfunction "EP_9") (pintype "power_in"))
      (node (ref "U5") (pin "2") (pinfunction "VSS_2") (pintype "power_in"))
    )
    (net (code "15") (name "GPIO8") (class "Default")
      (node (ref "R1") (pin "1") (pinfunction "1_1") (pintype "passive"))
      (node (ref "U2") (pin "10") (pinfunction "IO8_10") (pintype "bidirectional"))
    )
    (net (code "16") (name "I2C_PW") (class "Default")
      (node (ref "C1") (pin "1") (pinfunction "1_1") (pintype "passive"))
      (node (ref "C2") (pin "1") (pinfunction "1_1") (pintype "passive"))
      (node (ref "U2") (pin "17") (pinfunction "IO19_17") (pintype "bidirectional"))
    )
    (net (code "17") (name "INT_RTC") (class "Default")
      (node (ref "INT_RTC") (pin "TP") (pinfunction "TP_TP") (pintype "input"))
      (node (ref "R1_PINH1") (pin "1") (pinfunction "1_1") (pintype "passive"))
      (node (ref "U2") (pin "8") (pinfunction "IO0_8") (pintype "bidirectional"))
      (node (ref "U3") (pin "3") (pinfunction "SQW/~{INT}_3") (pintype "output"))
    )
    (net (code "18") (name "IO{slash}BOOT") (class "Default")
      (node (ref "BOOT_BUTTON") (pin "3") (pinfunction "3_3") (pintype "passive"))
      (node (ref "BOOT_BUTTON") (pin "4") (pinfunction "4_4") (pintype "passive"))
      (node (ref "C6") (pin "1") (pinfunction "1_1") (pintype "passive"))
      (node (ref "R_BOOT") (pin "2") (pinfunction "2_2") (pintype "passive"))
      (node (ref "U2") (pin "15") (pinfunction "IO9_15") (pintype "bidirectional"))
    )
    (net (code "19") (name "IO{slash}CHANGE") (class "Default")
      (node (ref "C10") (pin "1") (pinfunction "1_1") (pintype "passive"))
      (node (ref "CHANGE_BUTTON") (pin "3") (pinfunction "3_3") (pintype "passive"))
      (node (ref "CHANGE_BUTTON") (pin "4") (pinfunction "4_4") (pintype "passive"))
      (node (ref "R_CHANGE") (pin "2") (pinfunction "2_2") (pintype "passive"))
      (node (ref "U2") (pin "23") (pinfunction "IO15_23") (pintype "bidirectional"))
    )
    (net (code "20") (name "MISO") (class "Default")
      (node (ref "D12") (pin "2") (pinfunction "2_2") (pintype "passive"))
      (node (ref "J4") (pin "P7") (pinfunction "DAT0_P7") (pintype "bidirectional"))
      (node (ref "MISO") (pin "TP") (pinfunction "TP_TP") (pintype "input"))
      (node (ref "R8") (pin "1") (pinfunction "1_1") (pintype "passive"))
      (node (ref "U1") (pin "2") (pinfunction "DO(IO1)_2") (pintype "bidirectional"))
      (node (ref "U2") (pin "27") (pinfunction "IO2_27") (pintype "bidirectional"))
    )
    (net (code "21") (name "MOSI") (class "Default")
      (node (ref "D11") (pin "2") (pinfunction "2_2") (pintype "passive"))
      (node (ref "J1") (pin "14") (pinfunction "14_14") (pintype "bidirectional"))
      (node (ref "J4") (pin "P3") (pinfunction "CMD_P3") (pintype "bidirectional"))
      (node (ref "MOSI") (pin "TP") (pinfunction "TP_TP") (pintype "input"))
      (node (ref "R7") (pin "1") (pinfunction "1_1") (pintype "passive"))
      (node (ref "U1") (pin "5") (pinfunction "DI(IO0)_5") (pintype "bidirectional"))
      (node (ref "U2") (pin "7") (pinfunction "IO7_7") (pintype "bidirectional"))
    )
    (net (code "22") (name "Net-(CHG_LED-PadC)") (class "Default")
      (node (ref "CHG_LED") (pin "C") (pinfunction "C_C") (pintype "passive"))
      (node (ref "R1_BAT") (pin "2") (pinfunction "2_2") (pintype "passive"))
    )
    (net (code "23") (name "Net-(D2-CATHODE)") (class "Default")
      (node (ref "C1_BAT1") (pin "1") (pinfunction "1_1") (pintype "passive"))
      (node (ref "D2") (pin "1") (pinfunction "CATHODE_1") (pintype "bidirectional"))
      (node (ref "IC4") (pin "1") (pinfunction "VIN_1") (pintype "bidirectional"))
      (node (ref "IC4") (pin "3") (pinfunction "CE_3") (pintype "bidirectional"))
      (node (ref "Q1") (pin "2") (pinfunction "S_2") (pintype "bidirectional"))
    )
    (net (code "24") (name "Net-(D3-K)") (class "Default")
      (node (ref "C4") (pin "1") (pinfunction "1_1") (pintype "passive"))
      (node (ref "D3") (pin "1") (pinfunction "K_1") (pintype "bidirectional"))
      (node (ref "D4") (pin "2") (pinfunction "A_2") (pintype "bidirectional"))
    )
    (net (code "25") (name "Net-(D7-CATHODE)") (class "Default")
      (node (ref "D7") (pin "1") (pinfunction "CATHODE_1") (pintype "bidirectional"))
      (node (ref "R_CAPACITOR") (pin "1") (pinfunction "1_1") (pintype "passive"))
    )
    (net (code "26") (name "Net-(EPD_C1-Pad2)") (class "Default")
      (node (ref "EPD_C1") (pin "2") (pinfunction "2_2") (pintype "passive"))
      (node (ref "J1") (pin "4") (pinfunction "4_4") (pintype "bidirectional"))
    )
    (net (code "27") (name "Net-(EPD_C2-Pad2)") (class "Default")
      (node (ref "EPD_C2") (pin "2") (pinfunction "2_2") (pintype "passive"))
      (node (ref "J1") (pin "5") (pinfunction "5_5") (pintype "bidirectional"))
    )
    (net (code "28") (name "Net-(EPD_C6-Pad2)") (class "Default")
      (node (ref "EPD_C6") (pin "2") (pinfunction "2_2") (pintype "passive"))
      (node (ref "J1") (pin "18") (pinfunction "18_18") (pintype "bidirectional"))
    )
    (net (code "29") (name "Net-(EPD_C7-Pad2)") (class "Default")
      (node (ref "EPD_C7") (pin "2") (pinfunction "2_2") (pintype "passive"))
      (node (ref "J1") (pin "19") (pinfunction "19_19") (pintype "bidirectional"))
    )
    (net (code "30") (name "Net-(EPD_C8-Pad2)") (class "Default")
      (node (ref "EPD_C8") (pin "2") (pinfunction "2_2") (pintype "passive"))
      (node (ref "J1") (pin "20") (pinfunction "20_20") (pintype "bidirectional"))
    )
    (net (code "31") (name "Net-(EPD_C10-Pad2)") (class "Default")
      (node (ref "EPD_C10") (pin "2") (pinfunction "2_2") (pintype "passive"))
      (node (ref "J1") (pin "22") (pinfunction "22_22") (pintype "bidirectional"))
    )
    (net (code "32") (name "Net-(EPD_C12-Pad2)") (class "Default")
      (node (ref "EPD_C12") (pin "2") (pinfunction "2_2") (pintype "passive"))
      (node (ref "J1") (pin "24") (pinfunction "24_24") (pintype "bidirectional"))
    )
    (net (code "33") (name "Net-(IC1-CT)") (class "Default")
      (node (ref "C_DELAY") (pin "1") (pinfunction "1_1") (pintype "passive"))
      (node (ref "IC1") (pin "5") (pinfunction "CT_5") (pintype "bidirectional"))
    )
    (net (code "34") (name "Net-(J2-PadA5)") (class "Default")
      (node (ref "J2") (pin "A5") (pinfunction "A5_A5") (pintype "bidirectional"))
      (node (ref "R2-USB1") (pin "2") (pinfunction "2_2") (pintype "passive"))
    )
    (net (code "35") (name "Net-(J2-PadB5)") (class "Default")
      (node (ref "J2") (pin "B5") (pinfunction "B5_B5") (pintype "bidirectional"))
      (node (ref "R2-USB") (pin "1") (pinfunction "1_1") (pintype "passive"))
    )
    (net (code "36") (name "Net-(U5-PROG)") (class "Default")
      (node (ref "R2_BAT") (pin "2") (pinfunction "2_2") (pintype "passive"))
      (node (ref "U5") (pin "5") (pinfunction "PROG_5") (pintype "input"))
    )
    (net (code "37") (name "Net-(U5-STAT)") (class "Default")
      (node (ref "R1_BAT") (pin "1") (pinfunction "1_1") (pintype "passive"))
      (node (ref "U5") (pin "1") (pinfunction "STAT_1") (pintype "output"))
    )
    (net (code "38") (name "PREVGH") (class "Default")
      (node (ref "D5") (pin "1") (pinfunction "K_1") (pintype "bidirectional"))
      (node (ref "EPD_C9") (pin "2") (pinfunction "2_2") (pintype "passive"))
      (node (ref "J1") (pin "21") (pinfunction "21_21") (pintype "bidirectional"))
    )
    (net (code "39") (name "PREVGL") (class "Default")
      (node (ref "D3") (pin "2") (pinfunction "A_2") (pintype "bidirectional"))
      (node (ref "EPD_C11") (pin "2") (pinfunction "2_2") (pintype "passive"))
      (node (ref "J1") (pin "23") (pinfunction "23_23") (pintype "bidirectional"))
    )
    (net (code "40") (name "RESE") (class "Default")
      (node (ref "J1") (pin "3") (pinfunction "3_3") (pintype "bidirectional"))
      (node (ref "Q3") (pin "2") (pinfunction "S_2") (pintype "bidirectional"))
      (node (ref "R3") (pin "1") (pinfunction "1_1") (pintype "passive"))
    )
    (net (code "41") (name "RESE'") (class "Default")
      (node (ref "R2") (pin "2") (pinfunction "2_2") (pintype "passive"))
      (node (ref "R3") (pin "2") (pinfunction "2_2") (pintype "passive"))
      (node (ref "SJ1") (pin "2") (pinfunction "2_2") (pintype "passive"))
    )
    (net (code "42") (name "RESET") (class "Default")
      (node (ref "C5") (pin "1") (pinfunction "1_1") (pintype "passive"))
      (node (ref "IC1") (pin "1") (pinfunction "VOUT_1") (pintype "bidirectional"))
      (node (ref "RESET_BUTTON") (pin "3") (pinfunction "3_3") (pintype "passive"))
      (node (ref "RESET_BUTTON") (pin "4") (pinfunction "4_4") (pintype "passive"))
      (node (ref "R_RESET") (pin "2") (pinfunction "2_2") (pintype "passive"))
      (node (ref "U2") (pin "3") (pinfunction "EN_3") (pintype "input"))
    )
    (net (code "43") (name "RTC_RST") (class "Default")
      (node (ref "U2") (pin "16") (pinfunction "IO18_16") (pintype "bidirectional"))
      (node (ref "U3") (pin "4") (pinfunction "~{RST}_4") (pintype "input"))
    )
    (net (code "44") (name "RX") (class "Default")
      (node (ref "RX") (pin "TP") (pinfunction "TP_TP") (pintype "input"))
      (node (ref "U2") (pin "24") (pinfunction "RXD0/GPIO17_24") (pintype "bidirectional"))
    )
    (net (code "45") (name "SCK") (class "Default")
      (node (ref "D10") (pin "2") (pinfunction "2_2") (pintype "passive"))
      (node (ref "J1") (pin "13") (pinfunction "13_13") (pintype "bidirectional"))
      (node (ref "J4") (pin "P5") (pinfunction "CLK_P5") (pintype "bidirectional"))
      (node (ref "R6") (pin "1") (pinfunction "1_1") (pintype "passive"))
      (node (ref "SCK") (pin "TP") (pinfunction "TP_TP") (pintype "input"))
      (node (ref "U1") (pin "6") (pinfunction "CLK_6") (pintype "input"))
      (node (ref "U2") (pin "6") (pinfunction "IO6_6") (pintype "bidirectional"))
    )
    (net (code "46") (name "SCL") (class "Default")
      (node (ref "J3") (pin "4") (pinfunction "4_4") (pintype "passive"))
      (node (ref "R2-PINH") (pin "1") (pinfunction "1_1") (pintype "passive"))
      (node (ref "SENSOR2") (pin "4") (pinfunction "SCK_4") (pintype "input"))
      (node (ref "U2") (pin "20") (pinfunction "IO22_20") (pintype "bidirectional"))
      (node (ref "U3") (pin "16") (pinfunction "SCL_16") (pintype "input"))
      (node (ref "U4") (pin "7") (pinfunction "SCL_7") (pintype "input"))
    )
    (net (code "47") (name "SDA") (class "Default")
      (node (ref "J3") (pin "3") (pinfunction "3_3") (pintype "passive"))
      (node (ref "R1-PINH") (pin "1") (pinfunction "1_1") (pintype "passive"))
      (node (ref "SENSOR2") (pin "3") (pinfunction "SDI_3") (pintype "bidirectional"))
      (node (ref "U2") (pin "19") (pinfunction "IO21_19") (pintype "bidirectional"))
      (node (ref "U3") (pin "15") (pinfunction "SDA_15") (pintype "bidirectional"))
      (node (ref "U4") (pin "8") (pinfunction "SDA_8") (pintype "bidirectional"))
    )
    (net (code "48") (name "SRC") (class "Default")
      (node (ref "C4") (pin "2") (pinfunction "2_2") (pintype "passive"))
      (node (ref "D5") (pin "2") (pinfunction "A_2") (pintype "bidirectional"))
      (node (ref "L1") (pin "1") (pinfunction "1_1") (pintype "passive"))
      (node (ref "Q3") (pin "3") (pinfunction "D_3") (pintype "bidirectional"))
    )
    (net (code "49") (name "SS_SD") (class "Default")
      (node (ref "D8") (pin "2") (pinfunction "2_2") (pintype "passive"))
      (node (ref "J4") (pin "P2") (pinfunction "CD/DAT3_P2") (pintype "bidirectional"))
      (node (ref "R10") (pin "1") (pinfunction "1_1") (pintype "passive"))
      (node (ref "U2") (pin "4") (pinfunction "IO4_4") (pintype "bidirectional"))
    )
    (net (code "50") (name "TX") (class "Default")
      (node (ref "TX") (pin "TP") (pinfunction "TP_TP") (pintype "input"))
      (node (ref "U2") (pin "25") (pinfunction "TXD0/GPIO16_25") (pintype "bidirectional"))
    )
    (net (code "51") (name "USB_D+") (class "Default")
      (node (ref "D1") (pin "4") (pinfunction "I/O2_2_4") (pintype "bidirectional"))
      (node (ref "U2") (pin "14") (pinfunction "IO13_14") (pintype "bidirectional"))
    )
    (net (code "52") (name "USB_D-") (class "Default")
      (node (ref "D1") (pin "6") (pinfunction "I/O1_2_6") (pintype "bidirectional"))
      (node (ref "U2") (pin "13") (pinfunction "IO12_13") (pintype "bidirectional"))
    )
    (net (code "53") (name "VBAT") (class "Default")
      (node (ref "C2_BAT") (pin "1") (pinfunction "1_1") (pintype "passive"))
      (node (ref "Q1") (pin "3") (pinfunction "D_3") (pintype "bidirectional"))
      (node (ref "U4") (pin "2") (pinfunction "CELL_2") (pintype "power_in"))
      (node (ref "U4") (pin "3") (pinfunction "VDD_3") (pintype "power_in"))
      (node (ref "U5") (pin "3") (pinfunction "VBAT_3") (pintype "power_in"))
      (node (ref "VBAT") (pin "TP") (pinfunction "TP_TP") (pintype "input"))
    )
    (net (code "54") (name "VBUS") (class "Default")
      (node (ref "C1_BAT") (pin "1") (pinfunction "1_1") (pintype "passive"))
      (node (ref "C4_USB") (pin "1") (pinfunction "1_1") (pintype "passive"))
      (node (ref "C5_USB") (pin "1") (pinfunction "1_1") (pintype "passive"))
      (node (ref "CHG_LED") (pin "A") (pinfunction "A_A") (pintype "passive"))
      (node (ref "D1") (pin "2") (pinfunction "GND_2") (pintype "bidirectional"))
      (node (ref "D2") (pin "2") (pinfunction "ANODE_2") (pintype "bidirectional"))
      (node (ref "PFMF.050.1") (pin "2") (pinfunction "2_2") (pintype "passive"))
      (node (ref "Q1") (pin "1") (pinfunction "G_1") (pintype "bidirectional"))
      (node (ref "R1_PWRUSB") (pin "2") (pinfunction "2_2") (pintype "passive"))
      (node (ref "U5") (pin "4") (pinfunction "VIN_4") (pintype "power_in"))
      (node (ref "VBUS") (pin "TP") (pinfunction "TP_TP") (pintype "input"))
    )
    (net (code "55") (name "VRTC") (class "Default")
      (node (ref "C10_SUPERCAP") (pin "1") (pinfunction "1_1") (pintype "passive"))
      (node (ref "C8") (pin "1") (pinfunction "1_1") (pintype "passive"))
      (node (ref "R_CAPACITOR") (pin "2") (pinfunction "2_2") (pintype "passive"))
      (node (ref "U3") (pin "14") (pinfunction "VBAT_14") (pintype "power_in"))
    )
    (net (code "56") (name "VUSB") (class "Default")
      (node (ref "J2") (pin "A4") (pinfunction "A4_A4") (pintype "bidirectional"))
      (node (ref "J2") (pin "A9") (pinfunction "A9_A9") (pintype "bidirectional"))
      (node (ref "J2") (pin "B4") (pinfunction "B4_B4") (pintype "bidirectional"))
      (node (ref "J2") (pin "B9") (pinfunction "B9_B9") (pintype "bidirectional"))
      (node (ref "PFMF.050.1") (pin "1") (pinfunction "1_1") (pintype "passive"))
    )
    (net (code "57") (name "unconnected-(IC1-NC-Pad4)") (class "Default")
      (node (ref "IC1") (pin "4") (pinfunction "NC_4") (pintype "no_connect"))
    )
    (net (code "58") (name "unconnected-(IC4-NC-Pad4)") (class "Default")
      (node (ref "IC4") (pin "4") (pinfunction "NC_4") (pintype "no_connect"))
    )
    (net (code "59") (name "unconnected-(J1-Pad1)") (class "Default")
      (node (ref "J1") (pin "1") (pinfunction "1_1") (pintype "bidirectional"))
    )
    (net (code "60") (name "unconnected-(J1-Pad6)") (class "Default")
      (node (ref "J1") (pin "6") (pinfunction "6_6") (pintype "bidirectional"))
    )
    (net (code "61") (name "unconnected-(J1-Pad7)") (class "Default")
      (node (ref "J1") (pin "7") (pinfunction "7_7") (pintype "bidirectional"))
    )
    (net (code "62") (name "unconnected-(J2-PadA8)") (class "Default")
      (node (ref "J2") (pin "A8") (pinfunction "A8_A8") (pintype "bidirectional"))
    )
    (net (code "63") (name "unconnected-(J2-PadB8)") (class "Default")
      (node (ref "J2") (pin "B8") (pinfunction "B8_B8") (pintype "bidirectional"))
    )
    (net (code "64") (name "unconnected-(J4-DAT1-PadP8)") (class "Default")
      (node (ref "J4") (pin "P8") (pinfunction "DAT1_P8") (pintype "bidirectional"))
    )
    (net (code "65") (name "unconnected-(J4-DAT2-PadP1)") (class "Default")
      (node (ref "J4") (pin "P1") (pinfunction "DAT2_P1") (pintype "bidirectional"))
    )
    (net (code "66") (name "unconnected-(J4-DETECTION_1-PadS1)") (class "Default")
      (node (ref "J4") (pin "S1") (pinfunction "DETECTION_1_S1") (pintype "bidirectional"))
    )
    (net (code "67") (name "unconnected-(J4-DETECTION_2-PadS2)") (class "Default")
      (node (ref "J4") (pin "S2") (pinfunction "DETECTION_2_S2") (pintype "bidirectional"))
    )
    (net (code "68") (name "unconnected-(U2-NC-Pad22)") (class "Default")
      (node (ref "U2") (pin "22") (pinfunction "NC_22") (pintype "no_connect"))
    )
    (net (code "69") (name "unconnected-(U4-~{ALERT}-Pad5)") (class "Default")
      (node (ref "U4") (pin "5") (pinfunction "~{ALERT}_5") (pintype "output"))
    )
  )
)
